# 4e_-_Brake_Detection.net
KiCad netlist of a schematic drawn in Altium Designer
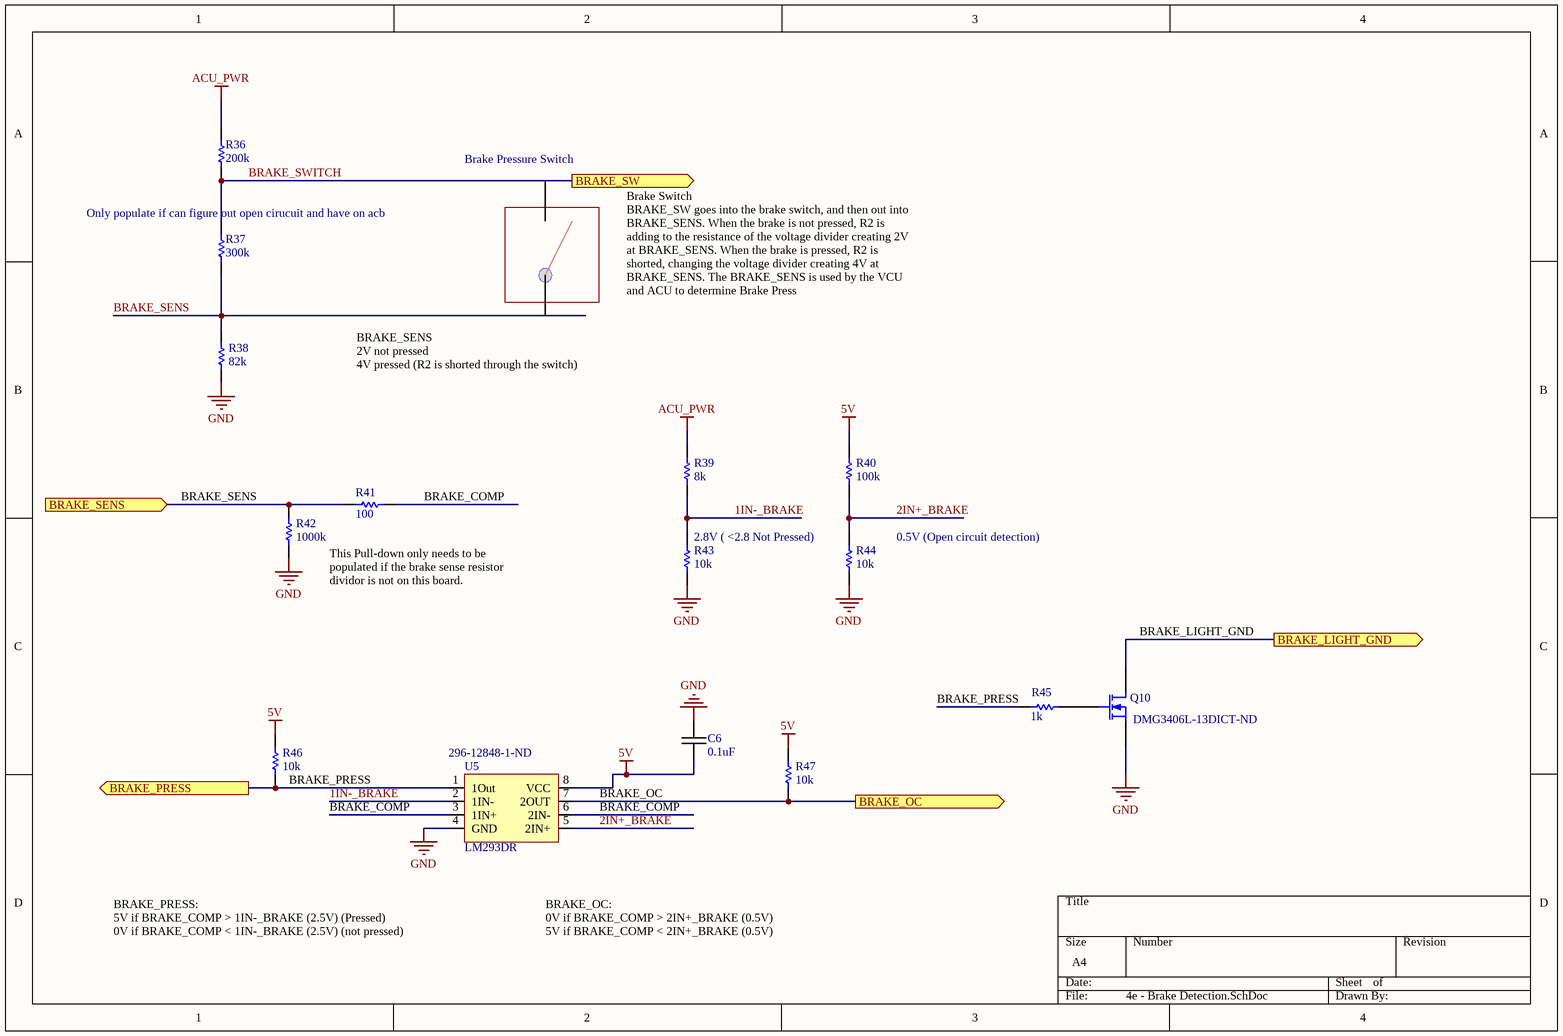
[diagram p0: 4e - Brake Detection.SchDoc]

(export (version "E")
  (design (tool "Eeschema 10.0.6"))
  (components
    (comp (ref "C6")
      (value "0.1uF")
      (footprint "1608[0603]")
      (description "CAP CER 0.1UF 50V X7R 0603")
      (fields
        (field (name "MANUFACTURER") "Kemet")
        (field (name "MANUFACTURER PART NUMBER") "C0603C104K5RACAUTO")
      )
      (libsource (lib "vh_altium_library") (part "0805C-100nF-25V-X7R-MUR"))
    )
    (comp (ref "Q10")
      (value "~")
      (footprint "SOT-23_N")
      (description "N-Channel MOSFET")
      (fields
        (field (name "MANUFACTURER") "Infineon Technologies")
        (field (name "SUPPLIER PART NUMBER 1") "DMG3406L-13DICT-ND")
        (field (name "PUBLISHER") "Altium Limited")
      )
      (libsource (lib "Miscellaneous Devices") (part "MOSFET-N"))
    )
    (comp (ref "R36")
      (value "200k")
      (footprint "1608[0603]")
      (description "RES SMD 10K OHM 5% 1/4W 0603")
      (fields
        (field (name "MANUFACTURER") "Rohm Semiconductor")
        (field (name "MANUFACTURER PART NUMBER") "ESR03EZPJ103")
        (field (name "PUBLISHER") "Altium Limited")
      )
      (libsource (lib "Miscellaneous Devices") (part "Res1"))
    )
    (comp (ref "R37")
      (value "300k")
      (footprint "1608[0603]")
      (description "RES SMD 10K OHM 5% 1/4W 0603")
      (fields
        (field (name "MANUFACTURER") "Rohm Semiconductor")
        (field (name "MANUFACTURER PART NUMBER") "ESR03EZPJ103")
        (field (name "PUBLISHER") "Altium Limited")
      )
      (libsource (lib "Miscellaneous Devices") (part "Res1"))
    )
    (comp (ref "R38")
      (value "82k")
      (footprint "1608[0603]")
      (description "RES SMD 10K OHM 5% 1/4W 0603")
      (fields
        (field (name "MANUFACTURER") "Rohm Semiconductor")
        (field (name "MANUFACTURER PART NUMBER") "ESR03EZPJ103")
        (field (name "PUBLISHER") "Altium Limited")
      )
      (libsource (lib "Miscellaneous Devices") (part "Res1"))
    )
    (comp (ref "R39")
      (value "Volt. Div. R1")
      (footprint "1608[0603]")
      (description "RES SMD 6.8K OHM 5% 1/4W 0603")
      (fields
        (field (name "MANUFACTURER") "Rohm Semiconductor")
        (field (name "MANUFACTURER PART NUMBER") "ESR03EZPJ682")
        (field (name "RESISTANCE (OHMS)") "8k")
      )
      (libsource (lib "Miscellaneous Devices") (part "Res1"))
    )
    (comp (ref "R40")
      (value "Volt. Div. R1")
      (footprint "1608[0603]")
      (description "RES SMD 6.8K OHM 5% 1/4W 0603")
      (fields
        (field (name "MANUFACTURER") "Rohm Semiconductor")
        (field (name "MANUFACTURER PART NUMBER") "ESR03EZPJ682")
        (field (name "RESISTANCE (OHMS)") "100k")
      )
      (libsource (lib "Miscellaneous Devices") (part "Res1"))
    )
    (comp (ref "R41")
      (value "100")
      (footprint "1608[0603]")
      (description "RES SMD 20K OHM 5% 1/4W 0603")
      (fields
        (field (name "MANUFACTURER") "Rohm Semiconductor")
        (field (name "MANUFACTURER PART NUMBER") "ESR03EZPJ203")
        (field (name "PUBLISHER") "Altium Limited")
      )
      (libsource (lib "Miscellaneous Devices") (part "Res1"))
    )
    (comp (ref "R42")
      (value "1000k")
      (footprint "1608[0603]")
      (description "RES SMD 20K OHM 5% 1/4W 0603")
      (fields
        (field (name "MANUFACTURER") "Rohm Semiconductor")
        (field (name "MANUFACTURER PART NUMBER") "ESR03EZPJ203")
        (field (name "PUBLISHER") "Altium Limited")
      )
      (libsource (lib "Miscellaneous Devices") (part "Res1"))
    )
    (comp (ref "R43")
      (value "10k")
      (footprint "1608[0603]")
      (description "RES SMD 20K OHM 5% 1/4W 0603")
      (fields
        (field (name "MANUFACTURER") "Rohm Semiconductor")
        (field (name "MANUFACTURER PART NUMBER") "ESR03EZPJ203")
        (field (name "PUBLISHER") "Altium Limited")
      )
      (libsource (lib "Miscellaneous Devices") (part "Res1"))
    )
    (comp (ref "R44")
      (value "10k")
      (footprint "1608[0603]")
      (description "RES SMD 20K OHM 5% 1/4W 0603")
      (fields
        (field (name "MANUFACTURER") "Rohm Semiconductor")
        (field (name "MANUFACTURER PART NUMBER") "ESR03EZPJ203")
        (field (name "PUBLISHER") "Altium Limited")
      )
      (libsource (lib "Miscellaneous Devices") (part "Res1"))
    )
    (comp (ref "R45")
      (value "1k")
      (footprint "RESC0603(1608)_L")
      (description "0603 (1608 Metric) Chip Resistor")
      (libsource (lib "Altium Content Vault") (part "RES_3"))
    )
    (comp (ref "R46")
      (value "10k")
      (footprint "1608[0603]")
      (description "RES SMD 20K OHM 5% 1/4W 0603")
      (fields
        (field (name "MANUFACTURER") "Rohm Semiconductor")
        (field (name "MANUFACTURER PART NUMBER") "ESR03EZPJ203")
        (field (name "PUBLISHER") "Altium Limited")
      )
      (libsource (lib "Miscellaneous Devices") (part "Res1"))
    )
    (comp (ref "R47")
      (value "10k")
      (footprint "1608[0603]")
      (description "RES SMD 20K OHM 5% 1/4W 0603")
      (fields
        (field (name "MANUFACTURER") "Rohm Semiconductor")
        (field (name "MANUFACTURER PART NUMBER") "ESR03EZPJ203")
        (field (name "PUBLISHER") "Altium Limited")
      )
      (libsource (lib "Miscellaneous Devices") (part "Res1"))
    )
    (comp (ref "U5")
      (value "LM293DR")
      (footprint "LM293DR")
      (description "IC Dual Comparator")
      (fields (field (name "SUPPLIER PART NUMBER 1") "296-12848-1-ND"))
      (libsource (lib "ACB_lib") (part "LM293DR"))
    )
  )
  (nets
    (net (code "1") (name "/1IN-_BRAKE") (class "Default")
      (node (ref "R39") (pin "1") (pinfunction "1_1") (pintype "passive"))
      (node (ref "R43") (pin "2") (pinfunction "2_2") (pintype "passive"))
      (node (ref "U5") (pin "2") (pinfunction "1IN-_2") (pintype "passive"))
    )
    (net (code "2") (name "/2IN+_BRAKE") (class "Default")
      (node (ref "R40") (pin "1") (pinfunction "1_1") (pintype "passive"))
      (node (ref "R44") (pin "2") (pinfunction "2_2") (pintype "passive"))
      (node (ref "U5") (pin "5") (pinfunction "2IN+_5") (pintype "passive"))
    )
    (net (code "3") (name "/BRAKE_COMP") (class "Default")
      (node (ref "R41") (pin "1") (pinfunction "1_1") (pintype "passive"))
      (node (ref "U5") (pin "3") (pinfunction "1IN+_3") (pintype "passive"))
      (node (ref "U5") (pin "6") (pinfunction "2IN-_6") (pintype "passive"))
    )
    (net (code "4") (name "/BRAKE_LIGHT_GND") (class "Default")
      (node (ref "Q10") (pin "3") (pinfunction "D_3") (pintype "passive"))
    )
    (net (code "5") (name "/BRAKE_OC") (class "Default")
      (node (ref "R47") (pin "1") (pinfunction "1_1") (pintype "passive"))
      (node (ref "U5") (pin "7") (pinfunction "2OUT_7") (pintype "passive"))
    )
    (net (code "6") (name "/BRAKE_PRESS") (class "Default")
      (node (ref "R45") (pin "1") (pinfunction "1_1") (pintype "passive"))
      (node (ref "R46") (pin "1") (pinfunction "1_1") (pintype "passive"))
      (node (ref "U5") (pin "1") (pinfunction "1Out_1") (pintype "passive"))
    )
    (net (code "7") (name "/BRAKE_SENS") (class "Default")
      (node (ref "R37") (pin "2") (pinfunction "2_2") (pintype "passive"))
      (node (ref "R38") (pin "2") (pinfunction "2_2") (pintype "passive"))
      (node (ref "R41") (pin "2") (pinfunction "2_2") (pintype "passive"))
      (node (ref "R42") (pin "2") (pinfunction "2_2") (pintype "passive"))
    )
    (net (code "8") (name "/BRAKE_SWITCH") (class "Default")
      (node (ref "R36") (pin "1") (pinfunction "1_1") (pintype "passive"))
      (node (ref "R37") (pin "1") (pinfunction "1_1") (pintype "passive"))
    )
    (net (code "9") (name "5V") (class "Default")
      (node (ref "C6") (pin "1") (pintype "passive"))
      (node (ref "R40") (pin "2") (pinfunction "2_2") (pintype "passive"))
      (node (ref "R46") (pin "2") (pinfunction "2_2") (pintype "passive"))
      (node (ref "R47") (pin "2") (pinfunction "2_2") (pintype "passive"))
      (node (ref "U5") (pin "8") (pinfunction "VCC_8") (pintype "passive"))
    )
    (net (code "10") (name "ACU_PWR") (class "Default")
      (node (ref "R36") (pin "2") (pinfunction "2_2") (pintype "passive"))
      (node (ref "R39") (pin "2") (pinfunction "2_2") (pintype "passive"))
    )
    (net (code "11") (name "GND") (class "Default")
      (node (ref "C6") (pin "2") (pintype "passive"))
      (node (ref "Q10") (pin "2") (pinfunction "S_2") (pintype "passive"))
      (node (ref "R38") (pin "1") (pinfunction "1_1") (pintype "passive"))
      (node (ref "R42") (pin "1") (pinfunction "1_1") (pintype "passive"))
      (node (ref "R43") (pin "1") (pinfunction "1_1") (pintype "passive"))
      (node (ref "R44") (pin "1") (pinfunction "1_1") (pintype "passive"))
      (node (ref "U5") (pin "4") (pinfunction "GND_4") (pintype "passive"))
    )
    (net (code "12") (name "Net-(Q10-G)") (class "Default")
      (node (ref "Q10") (pin "1") (pinfunction "G_1") (pintype "passive"))
      (node (ref "R45") (pin "2") (pinfunction "2_2") (pintype "passive"))
    )
  )
)
